# Sch_pwr_brd_pwr_sys.net
KiCad netlist of a schematic drawn in Altium Designer
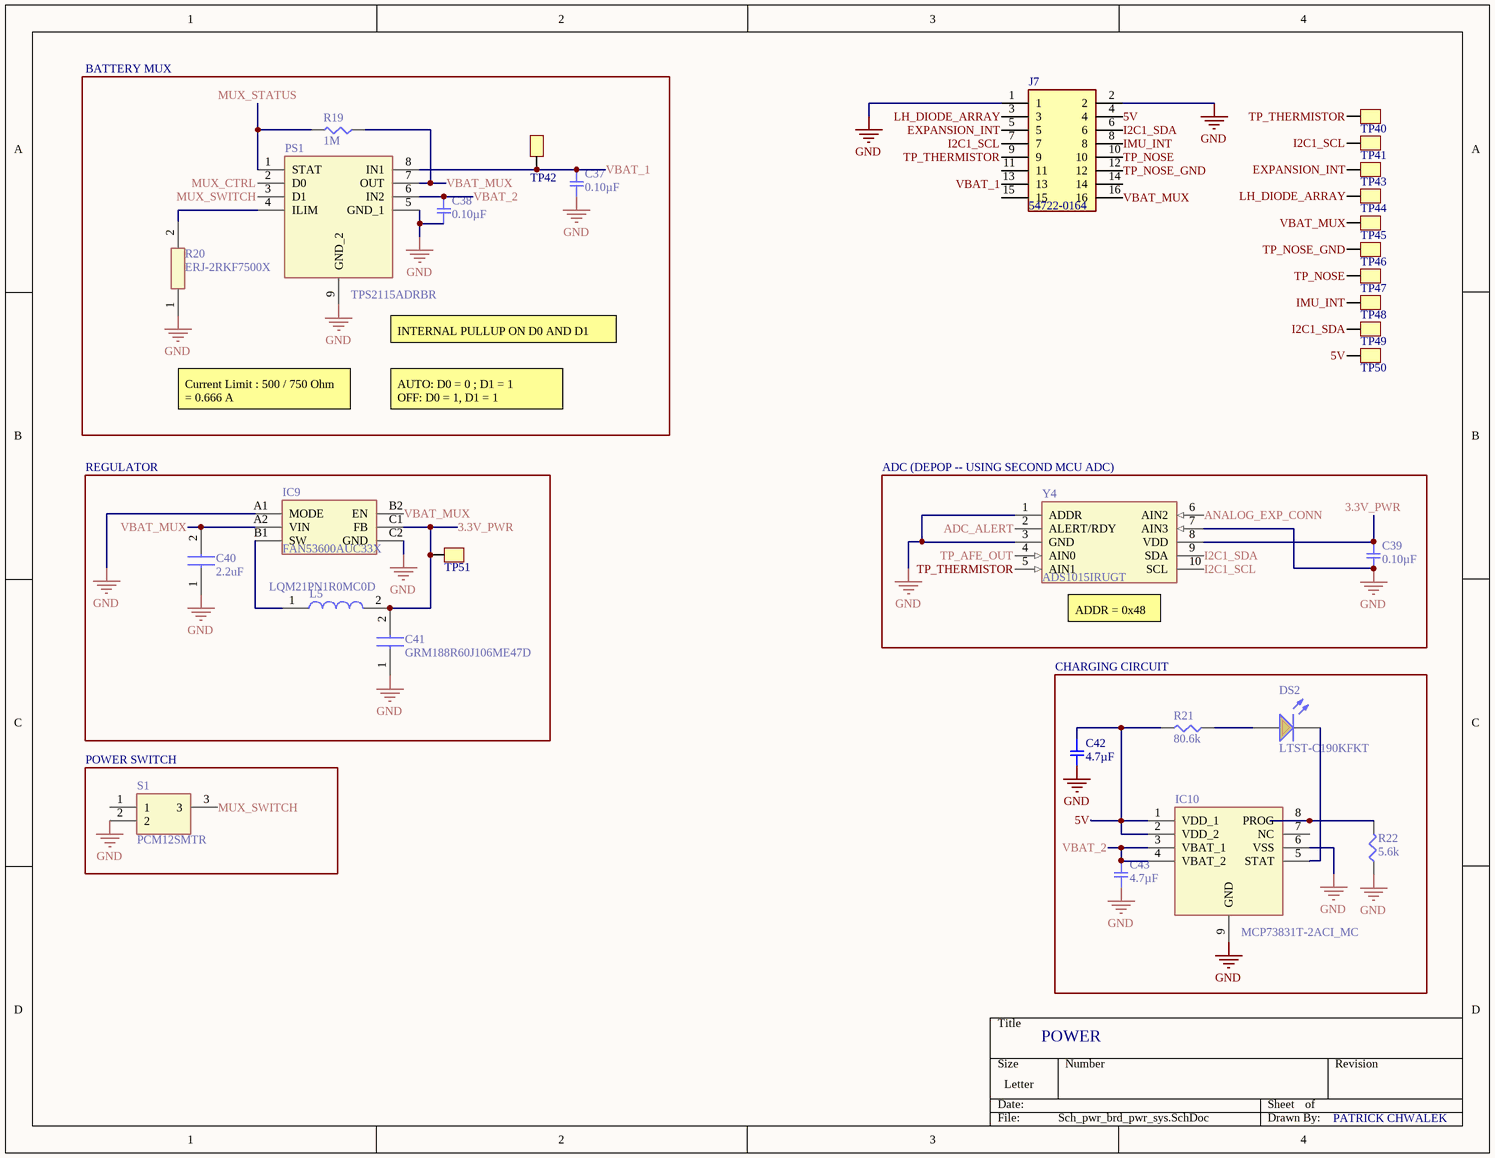
[diagram p0: Sch_pwr_brd_pwr_sys.SchDoc]

(export (version "E")
  (design (tool "Eeschema 10.0.6"))
  (components
    (comp (ref "C37")
      (value "0.10µF")
      (footprint "SMD-0402C")
      (description "CAP CER 0.1UF 16V X7R 0402")
      (fields
        (field (name "DIGI-KEY PART NUMBER") "490-4759-1-ND")
        (field (name "PART NUMBER") "GCM155R71C104KA55D")
      )
      (libsource (lib "capacitor_murata_0402") (part "GCM155R71C104KA55D"))
    )
    (comp (ref "C38")
      (value "0.10µF")
      (footprint "SMD-0402C")
      (description "CAP CER 0.1UF 16V X7R 0402")
      (fields
        (field (name "DIGI-KEY PART NUMBER") "490-4759-1-ND")
        (field (name "PART NUMBER") "GCM155R71C104KA55D")
      )
      (libsource (lib "capacitor_murata_0402") (part "GCM155R71C104KA55D"))
    )
    (comp (ref "C39")
      (value "0.10µF")
      (footprint "SMD-0402C")
      (description "CAP CER 0.1UF 16V X7R 0402")
      (fields
        (field (name "DIGI-KEY PART NUMBER") "490-4759-1-ND")
        (field (name "PART NUMBER") "GCM155R71C104KA55D")
      )
      (libsource (lib "capacitor_murata_0402") (part "GCM155R71C104KA55D"))
    )
    (comp (ref "C40")
      (value "2.2uF")
      (footprint "SamacSys:CAPC1005X55N")
      (description "Capacitor")
      (fields
        (field (name "MANUFACTURER_PART_NUMBER") "GRM155R60J225ME15D")
        (field (name "MOUSER PART NUMBER") "81-GRM155R60J225ME5D")
      )
      (libsource (lib "*") (part "GRM155R60J225ME15D"))
    )
    (comp (ref "C41")
      (value "GRM188R60J106ME47D")
      (footprint "custom_footprints:CAPC1608X09N")
      (description "Capacitor")
      (fields
        (field (name "MOUSER PART NUMBER") "81-GRM188R60J106ME47")
        (field (name "RS PART NUMBER") "7235543P")
      )
      (libsource (lib "*") (part "GRM188R60J106ME47D"))
    )
    (comp (ref "C42")
      (value "4.7µF")
      (footprint "SMD-0402C")
      (description "CAP CER 4.7UF 4V X5R 0402")
      (fields
        (field (name "DIGI-KEY PART NUMBER") "490-13231-1-ND")
        (field (name "PART NUMBER") "GRM153R60G475ME15D")
      )
      (libsource (lib "capacitor_murata_0402") (part "GRM153R60G475ME15D"))
    )
    (comp (ref "C43")
      (value "4.7µF")
      (footprint "SMD-0402C")
      (description "CAP CER 4.7UF 4V X5R 0402")
      (fields
        (field (name "DIGI-KEY PART NUMBER") "490-13231-1-ND")
        (field (name "PART NUMBER") "GRM153R60G475ME15D")
      )
      (libsource (lib "capacitor_murata_0402") (part "GRM153R60G475ME15D"))
    )
    (comp (ref "DS2")
      (value "LTST-C190KFKT")
      (footprint "LTST-C190KFKT_V")
      (description "LED Uni-Color Orange, 75 mW, 30 mA, -35 to 85 degC, 2-Pin SMD, RoHS, Tape and Reel")
      (fields (field (name "TOLERANCE") "1%"))
      (libsource (lib "Altium Content Vault") (part "LED-ORANGE-AK-2"))
    )
    (comp (ref "IC9")
      (value "FAN53600AUC33X")
      (footprint "SamacSys:BGA6C40P2X3_86X116X62")
      (description "Integrated Circuit")
      (fields (field (name "MOUSER PART NUMBER") "512-FAN53600AUC33X"))
      (libsource (lib "*") (part "FAN53600AUC33X"))
    )
    (comp (ref "IC10")
      (value "MCP73831T-2ACI_MC")
      (footprint "SamacSys:SON50P300X200X100-9N-D")
      (description "Integrated Circuit")
      (fields
        (field (name "MANUFACTURER_PART_NUMBER") "MCP73831T-2ACI/MC")
        (field (name "MOUSER PART NUMBER") "579-MCP73831T-2ACIMC")
      )
      (libsource (lib "*") (part "MCP73831T-2ACI_MC"))
    )
    (comp (ref "J7")
      (value "54722-0164")
      (footprint "SamacSys:54722-0164")
      (description "Connector")
      (fields (field (name "MOUSER PART NUMBER") "538-54722-0164") (field (name "RS PART NUMBER") "7206511"))
      (libsource (lib "*") (part "54722-0164"))
    )
    (comp (ref "L5")
      (value "LQM21PN1R0MC0D")
      (footprint "SamacSys:INDC2012X55N")
      (description "Inductor")
      (fields
        (field (name "MOUSER PART NUMBER") "81-LQM21PN1R0MC0D")
        (field (name "RS PART NUMBER") "7926388")
      )
      (libsource (lib "*") (part "LQM21PN1R0MC0D"))
    )
    (comp (ref "PS1")
      (value "TPS2115ADRBR")
      (footprint "SamacSys:SON65P300X300X100-9N-D")
      (description "Power Supply")
      (fields (field (name "MOUSER PART NUMBER") "595-TPS2115ADRBR"))
      (libsource (lib "*") (part "TPS2115ADRBR"))
    )
    (comp (ref "R19")
      (value "1M")
      (footprint "SMD-0402-RES")
      (description "RES SMD 1M OHM 5% 1/10W 0402")
      (fields (field (name "PART NUMBER") "ERJ-2GEJ105X") (field (name "DIGI-KEY PART NUMBER") "P1.0MJCT-ND"))
      (libsource (lib "Panasonic_ERJ_0402") (part "ERJ-2GEJ105X"))
    )
    (comp (ref "R20")
      (value "ERJ-2RKF7500X")
      (footprint "SamacSys:RESC1005X40N")
      (description "Resistor")
      (fields (field (name "MOUSER PART NUMBER") "667-ERJ-2RKF7500X"))
      (libsource (lib "*") (part "ERJ-2RKF7500X"))
    )
    (comp (ref "R21")
      (value "80.6k")
      (footprint "SMD-0402-RES")
      (description "RES SMD 80.6K OHM 1% 1/10W 0402")
      (fields
        (field (name "PART NUMBER") "ERJ-2RKF8062X")
        (field (name "DIGI-KEY PART NUMBER") "P80.6KLCT-ND")
      )
      (libsource (lib "Panasonic_ERJ_0402") (part "ERJ-2RKF8062X"))
    )
    (comp (ref "R22")
      (value "5.6k")
      (footprint "SMD-0402-RES")
      (description "RES SMD 5.6K OHM 5% 1/10W 0402")
      (fields (field (name "PART NUMBER") "ERJ-2GEJ562X") (field (name "DIGI-KEY PART NUMBER") "P5.6KJCT-ND"))
      (libsource (lib "Panasonic_ERJ_0402") (part "ERJ-2GEJ562X"))
    )
    (comp (ref "S1")
      (value "PCM12SMTR")
      (footprint "SamacSys:PCM12SMTR_1")
      (description "Switch")
      (fields (field (name "MOUSER PART NUMBER") "611-PCM12SMTR") (field (name "RS PART NUMBER") "7931721P"))
      (libsource (lib "*") (part "PCM12SMTR"))
    )
    (comp (ref "TP40")
      (value "TestPoint")
      (footprint "TestPoint_0.4mm")
      (libsource (lib "schematic_components") (part "TestPoint"))
    )
    (comp (ref "TP41")
      (value "TestPoint")
      (footprint "TestPoint_0.4mm")
      (libsource (lib "schematic_components") (part "TestPoint"))
    )
    (comp (ref "TP42")
      (value "TestPoint")
      (footprint "TestPoint_0.4mm")
      (libsource (lib "") (part "TestPoint_1"))
    )
    (comp (ref "TP43")
      (value "TestPoint")
      (footprint "TestPoint_0.4mm")
      (libsource (lib "schematic_components") (part "TestPoint"))
    )
    (comp (ref "TP44")
      (value "TestPoint")
      (footprint "TestPoint_0.4mm")
      (libsource (lib "schematic_components") (part "TestPoint"))
    )
    (comp (ref "TP45")
      (value "TestPoint")
      (footprint "TestPoint_0.4mm")
      (libsource (lib "schematic_components") (part "TestPoint"))
    )
    (comp (ref "TP46")
      (value "TestPoint")
      (footprint "TestPoint_0.4mm")
      (libsource (lib "schematic_components") (part "TestPoint"))
    )
    (comp (ref "TP47")
      (value "TestPoint")
      (footprint "TestPoint_0.4mm")
      (libsource (lib "schematic_components") (part "TestPoint"))
    )
    (comp (ref "TP48")
      (value "TestPoint")
      (footprint "TestPoint_0.4mm")
      (libsource (lib "schematic_components") (part "TestPoint"))
    )
    (comp (ref "TP49")
      (value "TestPoint")
      (footprint "TestPoint_0.4mm")
      (libsource (lib "schematic_components") (part "TestPoint"))
    )
    (comp (ref "TP50")
      (value "TestPoint")
      (footprint "TestPoint_0.4mm")
      (libsource (lib "schematic_components") (part "TestPoint"))
    )
    (comp (ref "TP51")
      (value "TestPoint")
      (footprint "TestPoint_0.4mm")
      (libsource (lib "schematic_components") (part "TestPoint"))
    )
    (comp (ref "Y4")
      (value "ADS1015IRUGT")
      (footprint "SamacSys:ADS7142IRUGT")
      (description "Crystal or Oscillator")
      (fields
        (field (name "MOUSER PART NUMBER") "595-ADS1015IRUGT")
        (field (name "RS PART NUMBER") "7321496")
      )
      (libsource (lib "*") (part "ADS1015IRUGT"))
    )
  )
  (nets
    (net (code "1") (name "/3.3V_PWR") (class "Default")
      (node (ref "C39") (pin "1") (pinfunction "1_1") (pintype "passive"))
      (node (ref "C41") (pin "2") (pinfunction "2_2") (pintype "passive"))
      (node (ref "IC9") (pin "C1") (pinfunction "FB_C1") (pintype "passive"))
      (node (ref "L5") (pin "2") (pinfunction "2_2") (pintype "passive"))
      (node (ref "TP51") (pin "1") (pinfunction "1_1") (pintype "passive"))
      (node (ref "Y4") (pin "8") (pinfunction "VDD_8") (pintype "power_in"))
    )
    (net (code "2") (name "/5V") (class "Default")
      (node (ref "C42") (pin "1") (pinfunction "1_1") (pintype "passive"))
      (node (ref "IC10") (pin "1") (pinfunction "VDD_1_1") (pintype "passive"))
      (node (ref "IC10") (pin "2") (pinfunction "VDD_2_2") (pintype "passive"))
      (node (ref "J7") (pin "4") (pinfunction "4_4") (pintype "passive"))
      (node (ref "R21") (pin "2") (pinfunction "2_2") (pintype "passive"))
      (node (ref "TP50") (pin "1") (pinfunction "1_1") (pintype "passive"))
    )
    (net (code "3") (name "/ADC_ALERT") (class "Default")
      (node (ref "Y4") (pin "2") (pinfunction "ALERT/RDY_2") (pintype "passive"))
    )
    (net (code "4") (name "/ANALOG_EXP_CONN") (class "Default")
      (node (ref "Y4") (pin "6") (pinfunction "AIN2_6") (pintype "input"))
    )
    (net (code "5") (name "/EXPANSION_INT") (class "Default")
      (node (ref "J7") (pin "5") (pinfunction "5_5") (pintype "passive"))
      (node (ref "TP43") (pin "1") (pinfunction "1_1") (pintype "passive"))
    )
    (net (code "6") (name "/I2C1_SCL") (class "Default")
      (node (ref "J7") (pin "7") (pinfunction "7_7") (pintype "passive"))
      (node (ref "TP41") (pin "1") (pinfunction "1_1") (pintype "passive"))
      (node (ref "Y4") (pin "10") (pinfunction "SCL_10") (pintype "passive"))
    )
    (net (code "7") (name "/I2C1_SDA") (class "Default")
      (node (ref "J7") (pin "6") (pinfunction "6_6") (pintype "passive"))
      (node (ref "TP49") (pin "1") (pinfunction "1_1") (pintype "passive"))
      (node (ref "Y4") (pin "9") (pinfunction "SDA_9") (pintype "passive"))
    )
    (net (code "8") (name "/IMU_INT") (class "Default")
      (node (ref "J7") (pin "8") (pinfunction "8_8") (pintype "passive"))
      (node (ref "TP48") (pin "1") (pinfunction "1_1") (pintype "passive"))
    )
    (net (code "9") (name "/LH_DIODE_ARRAY") (class "Default")
      (node (ref "J7") (pin "3") (pinfunction "3_3") (pintype "passive"))
      (node (ref "TP44") (pin "1") (pinfunction "1_1") (pintype "passive"))
    )
    (net (code "10") (name "/MUX_CTRL") (class "Default")
      (node (ref "PS1") (pin "2") (pinfunction "D0_2") (pintype "passive"))
    )
    (net (code "11") (name "/MUX_STATUS") (class "Default")
      (node (ref "PS1") (pin "1") (pinfunction "STAT_1") (pintype "passive"))
      (node (ref "R19") (pin "2") (pinfunction "2_2") (pintype "passive"))
    )
    (net (code "12") (name "/MUX_SWITCH") (class "Default")
      (node (ref "PS1") (pin "3") (pinfunction "D1_3") (pintype "passive"))
      (node (ref "S1") (pin "3") (pinfunction "3_3") (pintype "passive"))
    )
    (net (code "13") (name "/TP_AFE_OUT") (class "Default")
      (node (ref "Y4") (pin "4") (pinfunction "AIN0_4") (pintype "input"))
    )
    (net (code "14") (name "/TP_NOSE") (class "Default")
      (node (ref "J7") (pin "10") (pinfunction "10_10") (pintype "passive"))
      (node (ref "TP47") (pin "1") (pinfunction "1_1") (pintype "passive"))
    )
    (net (code "15") (name "/TP_NOSE_GND") (class "Default")
      (node (ref "J7") (pin "12") (pinfunction "12_12") (pintype "passive"))
      (node (ref "TP46") (pin "1") (pinfunction "1_1") (pintype "passive"))
    )
    (net (code "16") (name "/TP_THERMISTOR") (class "Default")
      (node (ref "J7") (pin "9") (pinfunction "9_9") (pintype "passive"))
      (node (ref "TP40") (pin "1") (pinfunction "1_1") (pintype "passive"))
      (node (ref "Y4") (pin "5") (pinfunction "AIN1_5") (pintype "input"))
    )
    (net (code "17") (name "/VBAT_1") (class "Default")
      (node (ref "C37") (pin "1") (pinfunction "1_1") (pintype "passive"))
      (node (ref "J7") (pin "13") (pinfunction "13_13") (pintype "passive"))
      (node (ref "PS1") (pin "8") (pinfunction "IN1_8") (pintype "passive"))
      (node (ref "TP42") (pin "1") (pinfunction "1_1") (pintype "passive"))
    )
    (net (code "18") (name "/VBAT_2") (class "Default")
      (node (ref "C38") (pin "1") (pinfunction "1_1") (pintype "passive"))
      (node (ref "C43") (pin "1") (pinfunction "1_1") (pintype "passive"))
      (node (ref "IC10") (pin "3") (pinfunction "VBAT_1_3") (pintype "passive"))
      (node (ref "IC10") (pin "4") (pinfunction "VBAT_2_4") (pintype "passive"))
      (node (ref "PS1") (pin "6") (pinfunction "IN2_6") (pintype "passive"))
    )
    (net (code "19") (name "/VBAT_MUX") (class "Default")
      (node (ref "C40") (pin "2") (pinfunction "2_2") (pintype "passive"))
      (node (ref "IC9") (pin "A2") (pinfunction "VIN_A2") (pintype "passive"))
      (node (ref "IC9") (pin "B2") (pinfunction "EN_B2") (pintype "passive"))
      (node (ref "J7") (pin "16") (pinfunction "16_16") (pintype "passive"))
      (node (ref "PS1") (pin "7") (pinfunction "OUT_7") (pintype "passive"))
      (node (ref "R19") (pin "1") (pinfunction "1_1") (pintype "passive"))
      (node (ref "TP45") (pin "1") (pinfunction "1_1") (pintype "passive"))
    )
    (net (code "20") (name "GND") (class "Default")
      (node (ref "C37") (pin "2") (pinfunction "2_2") (pintype "passive"))
      (node (ref "C38") (pin "2") (pinfunction "2_2") (pintype "passive"))
      (node (ref "C39") (pin "2") (pinfunction "2_2") (pintype "passive"))
      (node (ref "C40") (pin "1") (pinfunction "1_1") (pintype "passive"))
      (node (ref "C41") (pin "1") (pinfunction "1_1") (pintype "passive"))
      (node (ref "C42") (pin "2") (pinfunction "2_2") (pintype "passive"))
      (node (ref "C43") (pin "2") (pinfunction "2_2") (pintype "passive"))
      (node (ref "IC10") (pin "6") (pinfunction "VSS_6") (pintype "passive"))
      (node (ref "IC10") (pin "9") (pinfunction "GND_9") (pintype "passive"))
      (node (ref "IC9") (pin "A1") (pinfunction "MODE_A1") (pintype "passive"))
      (node (ref "IC9") (pin "C2") (pinfunction "GND_C2") (pintype "passive"))
      (node (ref "J7") (pin "1") (pinfunction "1_1") (pintype "passive"))
      (node (ref "J7") (pin "2") (pinfunction "2_2") (pintype "passive"))
      (node (ref "PS1") (pin "5") (pinfunction "GND_1_5") (pintype "passive"))
      (node (ref "PS1") (pin "9") (pinfunction "GND_2_9") (pintype "passive"))
      (node (ref "R20") (pin "1") (pinfunction "1_1") (pintype "passive"))
      (node (ref "R22") (pin "1") (pinfunction "1_1") (pintype "passive"))
      (node (ref "S1") (pin "2") (pinfunction "2_2") (pintype "passive"))
      (node (ref "Y4") (pin "1") (pinfunction "ADDR_1") (pintype "passive"))
      (node (ref "Y4") (pin "3") (pinfunction "GND_3") (pintype "power_in"))
      (node (ref "Y4") (pin "7") (pinfunction "AIN3_7") (pintype "input"))
    )
    (net (code "21") (name "Net-(DS2-A)") (class "Default")
      (node (ref "DS2") (pin "1") (pinfunction "A_1") (pintype "passive"))
      (node (ref "R21") (pin "1") (pinfunction "1_1") (pintype "passive"))
    )
    (net (code "22") (name "Net-(DS2-K)") (class "Default")
      (node (ref "DS2") (pin "2") (pinfunction "K_2") (pintype "passive"))
      (node (ref "IC10") (pin "5") (pinfunction "STAT_5") (pintype "passive"))
    )
    (net (code "23") (name "Net-(IC9-SW)") (class "Default")
      (node (ref "IC9") (pin "B1") (pinfunction "SW_B1") (pintype "passive"))
      (node (ref "L5") (pin "1") (pinfunction "1_1") (pintype "passive"))
    )
    (net (code "24") (name "Net-(IC10-PROG)") (class "Default")
      (node (ref "IC10") (pin "8") (pinfunction "PROG_8") (pintype "passive"))
      (node (ref "R22") (pin "2") (pinfunction "2_2") (pintype "passive"))
    )
    (net (code "25") (name "Net-(PS1-ILIM)") (class "Default")
      (node (ref "PS1") (pin "4") (pinfunction "ILIM_4") (pintype "passive"))
      (node (ref "R20") (pin "2") (pinfunction "2_2") (pintype "passive"))
    )
    (net (code "26") (name "unconnected-(IC10-NC-Pad7)") (class "Default")
      (node (ref "IC10") (pin "7") (pinfunction "NC_7") (pintype "passive"))
    )
    (net (code "27") (name "unconnected-(J7-Pad11)") (class "Default")
      (node (ref "J7") (pin "11") (pinfunction "11_11") (pintype "passive"))
    )
    (net (code "28") (name "unconnected-(J7-Pad14)") (class "Default")
      (node (ref "J7") (pin "14") (pinfunction "14_14") (pintype "passive"))
    )
    (net (code "29") (name "unconnected-(J7-Pad15)") (class "Default")
      (node (ref "J7") (pin "15") (pinfunction "15_15") (pintype "passive"))
    )
    (net (code "30") (name "unconnected-(S1-Pad1)") (class "Default")
      (node (ref "S1") (pin "1") (pinfunction "1_1") (pintype "passive"))
    )
  )
)
